# FCC_Connectors.net
KiCad netlist of a schematic drawn in Altium Designer
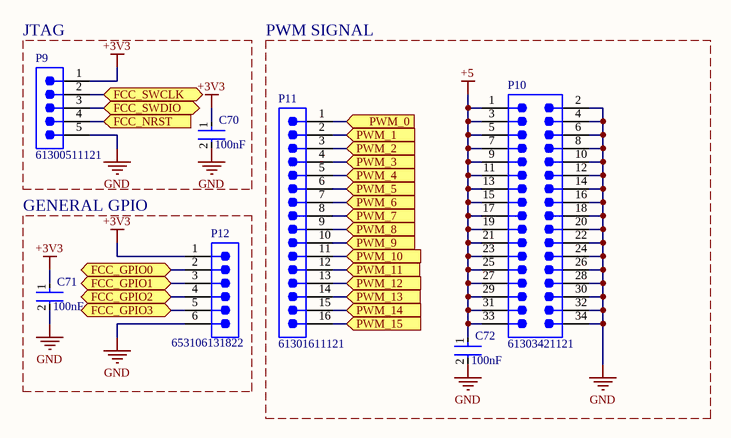
[diagram p0: FCC_Connectors.SchDoc]

(export (version "E")
  (design (tool "Eeschema 10.0.6"))
  (components
    (comp (ref "C70")
      (value "100nF")
      (footprint "FP-CGA3E-0_3-0_1-IPC_A")
      (description "Cap Ceramic 100nF 50V X7R 10% Pad SMD 0603 +125°C Automotive T/R")
      (fields (field (name "TOLERANCE") "10%") (field (name "VOLTAGE") "50V"))
      (libsource (lib "Altium Content Vault") (part "b4654b650e69147ec39a6b967a45e02"))
    )
    (comp (ref "C71")
      (value "100nF")
      (footprint "FP-CGA3E-0_3-0_1-IPC_A")
      (description "Cap Ceramic 100nF 50V X7R 10% Pad SMD 0603 +125°C Automotive T/R")
      (fields (field (name "TOLERANCE") "10%") (field (name "VOLTAGE") "50V"))
      (libsource (lib "Altium Content Vault") (part "b4654b650e69147ec39a6b967a45e02"))
    )
    (comp (ref "C72")
      (value "100nF")
      (footprint "FP-CGA3E-0_3-0_1-IPC_A")
      (description "Cap Ceramic 100nF 50V X7R 10% Pad SMD 0603 +125°C Automotive T/R")
      (fields (field (name "TOLERANCE") "10%") (field (name "VOLTAGE") "50V"))
      (libsource (lib "Altium Content Vault") (part "b4654b650e69147ec39a6b967a45e02"))
    )
    (comp (ref "P9")
      (value "61300511121")
      (footprint "61300511121")
      (libsource (lib "Altium Content Vault") (part "Header_Male_1R_05P"))
    )
    (comp (ref "P10")
      (value "61303421121")
      (footprint "61303421121")
      (libsource (lib "Altium Content Vault") (part "Header_Male_2R_34P"))
    )
    (comp (ref "P11")
      (value "61301611121")
      (footprint "61301611121")
      (libsource (lib "Altium Content Vault") (part "Header_Male_1R_16P"))
    )
    (comp (ref "P12")
      (value "653106131822")
      (footprint "653106131822")
      (libsource (lib "Altium Content Vault") (part "Header_Male_1R_06P"))
    )
  )
  (nets
    (net (code "1") (name "+3V3") (class "Default")
      (node (ref "C70") (pin "1") (pinfunction "1_1") (pintype "passive"))
      (node (ref "C71") (pin "1") (pinfunction "1_1") (pintype "passive"))
      (node (ref "P12") (pin "1") (pinfunction "1_1") (pintype "passive"))
      (node (ref "P9") (pin "1") (pinfunction "1_1") (pintype "passive"))
    )
    (net (code "2") (name "+5") (class "Default")
      (node (ref "C72") (pin "1") (pinfunction "1_1") (pintype "passive"))
      (node (ref "P10") (pin "1") (pinfunction "1_1") (pintype "passive"))
      (node (ref "P10") (pin "11") (pinfunction "11_11") (pintype "passive"))
      (node (ref "P10") (pin "13") (pinfunction "13_13") (pintype "passive"))
      (node (ref "P10") (pin "15") (pinfunction "15_15") (pintype "passive"))
      (node (ref "P10") (pin "17") (pinfunction "17_17") (pintype "passive"))
      (node (ref "P10") (pin "19") (pinfunction "19_19") (pintype "passive"))
      (node (ref "P10") (pin "21") (pinfunction "21_21") (pintype "passive"))
      (node (ref "P10") (pin "23") (pinfunction "23_23") (pintype "passive"))
      (node (ref "P10") (pin "25") (pinfunction "25_25") (pintype "passive"))
      (node (ref "P10") (pin "27") (pinfunction "27_27") (pintype "passive"))
      (node (ref "P10") (pin "29") (pinfunction "29_29") (pintype "passive"))
      (node (ref "P10") (pin "3") (pinfunction "3_3") (pintype "passive"))
      (node (ref "P10") (pin "31") (pinfunction "31_31") (pintype "passive"))
      (node (ref "P10") (pin "33") (pinfunction "33_33") (pintype "passive"))
      (node (ref "P10") (pin "5") (pinfunction "5_5") (pintype "passive"))
      (node (ref "P10") (pin "7") (pinfunction "7_7") (pintype "passive"))
      (node (ref "P10") (pin "9") (pinfunction "9_9") (pintype "passive"))
    )
    (net (code "3") (name "/FCC_GPIO0") (class "Default")
      (node (ref "P12") (pin "2") (pinfunction "2_2") (pintype "passive"))
    )
    (net (code "4") (name "/FCC_GPIO1") (class "Default")
      (node (ref "P12") (pin "3") (pinfunction "3_3") (pintype "passive"))
    )
    (net (code "5") (name "/FCC_GPIO2") (class "Default")
      (node (ref "P12") (pin "4") (pinfunction "4_4") (pintype "passive"))
    )
    (net (code "6") (name "/FCC_GPIO3") (class "Default")
      (node (ref "P12") (pin "5") (pinfunction "5_5") (pintype "passive"))
    )
    (net (code "7") (name "/FCC_NRST") (class "Default")
      (node (ref "P9") (pin "4") (pinfunction "4_4") (pintype "passive"))
    )
    (net (code "8") (name "/FCC_SWCLK") (class "Default")
      (node (ref "P9") (pin "2") (pinfunction "2_2") (pintype "passive"))
    )
    (net (code "9") (name "/FCC_SWDIO") (class "Default")
      (node (ref "P9") (pin "3") (pinfunction "3_3") (pintype "passive"))
    )
    (net (code "10") (name "/PWM_0") (class "Default")
      (node (ref "P11") (pin "1") (pinfunction "1_1") (pintype "passive"))
    )
    (net (code "11") (name "/PWM_1") (class "Default")
      (node (ref "P11") (pin "2") (pinfunction "2_2") (pintype "passive"))
    )
    (net (code "12") (name "/PWM_2") (class "Default")
      (node (ref "P11") (pin "3") (pinfunction "3_3") (pintype "passive"))
    )
    (net (code "13") (name "/PWM_3") (class "Default")
      (node (ref "P11") (pin "4") (pinfunction "4_4") (pintype "passive"))
    )
    (net (code "14") (name "/PWM_4") (class "Default")
      (node (ref "P11") (pin "5") (pinfunction "5_5") (pintype "passive"))
    )
    (net (code "15") (name "/PWM_5") (class "Default")
      (node (ref "P11") (pin "6") (pinfunction "6_6") (pintype "passive"))
    )
    (net (code "16") (name "/PWM_6") (class "Default")
      (node (ref "P11") (pin "7") (pinfunction "7_7") (pintype "passive"))
    )
    (net (code "17") (name "/PWM_7") (class "Default")
      (node (ref "P11") (pin "8") (pinfunction "8_8") (pintype "passive"))
    )
    (net (code "18") (name "/PWM_8") (class "Default")
      (node (ref "P11") (pin "9") (pinfunction "9_9") (pintype "passive"))
    )
    (net (code "19") (name "/PWM_9") (class "Default")
      (node (ref "P11") (pin "10") (pinfunction "10_10") (pintype "passive"))
    )
    (net (code "20") (name "/PWM_10") (class "Default")
      (node (ref "P11") (pin "11") (pinfunction "11_11") (pintype "passive"))
    )
    (net (code "21") (name "/PWM_11") (class "Default")
      (node (ref "P11") (pin "12") (pinfunction "12_12") (pintype "passive"))
    )
    (net (code "22") (name "/PWM_12") (class "Default")
      (node (ref "P11") (pin "13") (pinfunction "13_13") (pintype "passive"))
    )
    (net (code "23") (name "/PWM_13") (class "Default")
      (node (ref "P11") (pin "14") (pinfunction "14_14") (pintype "passive"))
    )
    (net (code "24") (name "/PWM_14") (class "Default")
      (node (ref "P11") (pin "15") (pinfunction "15_15") (pintype "passive"))
    )
    (net (code "25") (name "/PWM_15") (class "Default")
      (node (ref "P11") (pin "16") (pinfunction "16_16") (pintype "passive"))
    )
    (net (code "26") (name "GND") (class "Default")
      (node (ref "C70") (pin "2") (pinfunction "2_2") (pintype "passive"))
      (node (ref "C71") (pin "2") (pinfunction "2_2") (pintype "passive"))
      (node (ref "C72") (pin "2") (pinfunction "2_2") (pintype "passive"))
      (node (ref "P10") (pin "10") (pinfunction "10_10") (pintype "passive"))
      (node (ref "P10") (pin "12") (pinfunction "12_12") (pintype "passive"))
      (node (ref "P10") (pin "14") (pinfunction "14_14") (pintype "passive"))
      (node (ref "P10") (pin "16") (pinfunction "16_16") (pintype "passive"))
      (node (ref "P10") (pin "18") (pinfunction "18_18") (pintype "passive"))
      (node (ref "P10") (pin "2") (pinfunction "2_2") (pintype "passive"))
      (node (ref "P10") (pin "20") (pinfunction "20_20") (pintype "passive"))
      (node (ref "P10") (pin "22") (pinfunction "22_22") (pintype "passive"))
      (node (ref "P10") (pin "24") (pinfunction "24_24") (pintype "passive"))
      (node (ref "P10") (pin "26") (pinfunction "26_26") (pintype "passive"))
      (node (ref "P10") (pin "28") (pinfunction "28_28") (pintype "passive"))
      (node (ref "P10") (pin "30") (pinfunction "30_30") (pintype "passive"))
      (node (ref "P10") (pin "32") (pinfunction "32_32") (pintype "passive"))
      (node (ref "P10") (pin "34") (pinfunction "34_34") (pintype "passive"))
      (node (ref "P10") (pin "4") (pinfunction "4_4") (pintype "passive"))
      (node (ref "P10") (pin "6") (pinfunction "6_6") (pintype "passive"))
      (node (ref "P10") (pin "8") (pinfunction "8_8") (pintype "passive"))
      (node (ref "P12") (pin "6") (pinfunction "6_6") (pintype "passive"))
      (node (ref "P9") (pin "5") (pinfunction "5_5") (pintype "passive"))
    )
  )
)
